# CPULED.net
KiCad netlist of a schematic drawn in Altium Designer
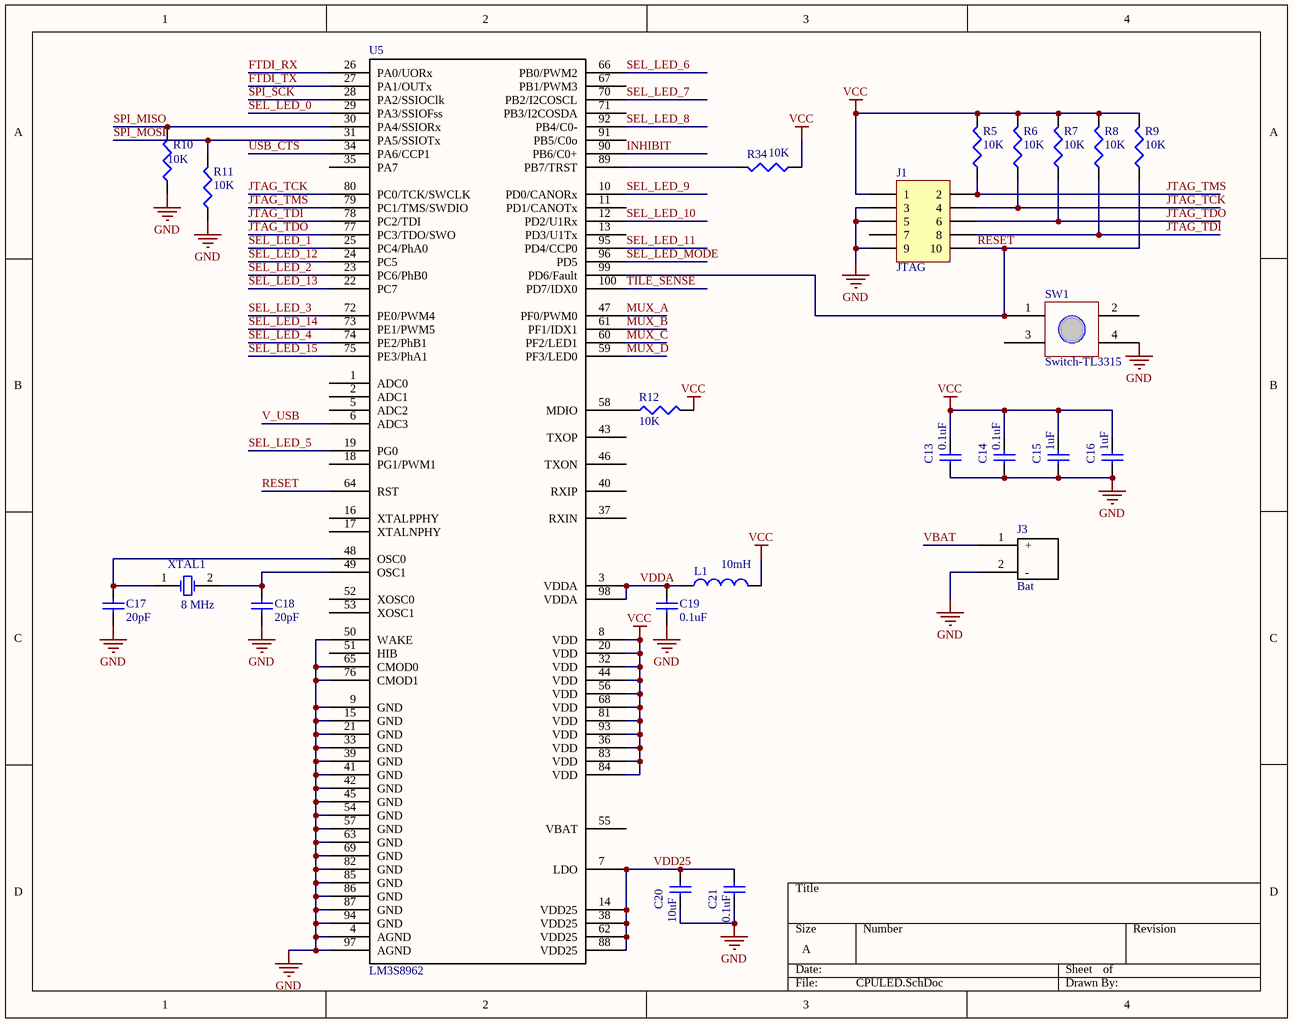
[diagram p0: CPULED.SchDoc]

(export (version "E")
  (design (tool "Eeschema 10.0.6"))
  (components
    (comp (ref "C13")
      (value "0.1uF")
      (footprint "CAPC1005L")
      (description "Capacitor (Semiconductor SIM Model)")
      (fields (field (name "Comment") "Cap Semi") (field (name "PUBLISHER") "Altium Limited"))
      (libsource (lib "Miscellaneous Devices") (part "Cap Semi"))
    )
    (comp (ref "C14")
      (value "0.1uF")
      (footprint "CAPC1005L")
      (description "Capacitor (Semiconductor SIM Model)")
      (fields (field (name "Comment") "Cap Semi") (field (name "PUBLISHER") "Altium Limited"))
      (libsource (lib "Miscellaneous Devices") (part "Cap Semi"))
    )
    (comp (ref "C15")
      (value "1uF")
      (footprint "CAPC1608L")
      (description "Capacitor (Semiconductor SIM Model)")
      (fields (field (name "Comment") "Cap Semi") (field (name "PUBLISHER") "Altium Limited"))
      (libsource (lib "Miscellaneous Devices") (part "Cap Semi"))
    )
    (comp (ref "C16")
      (value "1uF")
      (footprint "CAPC1608L")
      (description "Capacitor (Semiconductor SIM Model)")
      (fields (field (name "Comment") "Cap Semi") (field (name "PUBLISHER") "Altium Limited"))
      (libsource (lib "Miscellaneous Devices") (part "Cap Semi"))
    )
    (comp (ref "C17")
      (value "20pF")
      (footprint "CAPC1005L")
      (description "Capacitor (Semiconductor SIM Model)")
      (fields (field (name "Comment") "Cap Semi") (field (name "PUBLISHER") "Altium Limited"))
      (libsource (lib "Miscellaneous Devices") (part "Cap Semi"))
    )
    (comp (ref "C18")
      (value "20pF")
      (footprint "CAPC1005L")
      (description "Capacitor (Semiconductor SIM Model)")
      (fields (field (name "Comment") "Cap Semi") (field (name "PUBLISHER") "Altium Limited"))
      (libsource (lib "Miscellaneous Devices") (part "Cap Semi"))
    )
    (comp (ref "C19")
      (value "0.1uF")
      (footprint "CAPC1005L")
      (description "Capacitor (Semiconductor SIM Model)")
      (fields (field (name "Comment") "Cap Semi") (field (name "PUBLISHER") "Altium Limited"))
      (libsource (lib "Miscellaneous Devices") (part "Cap Semi"))
    )
    (comp (ref "C20")
      (value "10uF")
      (footprint "CAPC1608L")
      (description "Capacitor (Semiconductor SIM Model)")
      (fields (field (name "Comment") "Cap Semi") (field (name "PUBLISHER") "Altium Limited"))
      (libsource (lib "Miscellaneous Devices") (part "Cap Semi"))
    )
    (comp (ref "C21")
      (value "0.1uF")
      (footprint "CAPC1005L")
      (description "Capacitor (Semiconductor SIM Model)")
      (fields (field (name "Comment") "Cap Semi") (field (name "PUBLISHER") "Altium Limited"))
      (libsource (lib "Miscellaneous Devices") (part "Cap Semi"))
    )
    (comp (ref "J1")
      (value "JTAG")
      (footprint "JTAG-10")
      (description "Header, 5-Pin, Dual row, Right Angle")
      (fields (field (name "PUBLISHER") "Altium Limited"))
      (libsource (lib "Miscellaneous Connectors") (part "Header 5X2H"))
    )
    (comp (ref "J3")
      (value "Bat")
      (footprint "BatteryConnJST")
      (libsource (lib "mrone") (part "BatteryConnJST"))
    )
    (comp (ref "L1")
      (value "10mH")
      (footprint "INDC2012L")
      (description "Inductor")
      (fields (field (name "PUBLISHER") "Altium Limited"))
      (libsource (lib "Miscellaneous Devices") (part "Inductor"))
    )
    (comp (ref "R5")
      (value "10K")
      (footprint "RESC1608L")
      (description "Resistor")
      (fields (field (name "Comment") "Res3") (field (name "PUBLISHER") "Altium Limited"))
      (libsource (lib "Miscellaneous Devices") (part "Res3"))
    )
    (comp (ref "R6")
      (value "10K")
      (footprint "RESC1608L")
      (description "Resistor")
      (fields (field (name "Comment") "Res3") (field (name "PUBLISHER") "Altium Limited"))
      (libsource (lib "Miscellaneous Devices") (part "Res3"))
    )
    (comp (ref "R7")
      (value "10K")
      (footprint "RESC1608L")
      (description "Resistor")
      (fields (field (name "Comment") "Res3") (field (name "PUBLISHER") "Altium Limited"))
      (libsource (lib "Miscellaneous Devices") (part "Res3"))
    )
    (comp (ref "R8")
      (value "10K")
      (footprint "RESC1608L")
      (description "Resistor")
      (fields (field (name "Comment") "Res3") (field (name "PUBLISHER") "Altium Limited"))
      (libsource (lib "Miscellaneous Devices") (part "Res3"))
    )
    (comp (ref "R9")
      (value "10K")
      (footprint "RESC1608L")
      (description "Resistor")
      (fields (field (name "Comment") "Res3") (field (name "PUBLISHER") "Altium Limited"))
      (libsource (lib "Miscellaneous Devices") (part "Res3"))
    )
    (comp (ref "R10")
      (value "10K")
      (footprint "RESC1608L")
      (description "Resistor")
      (fields (field (name "Comment") "Res3") (field (name "PUBLISHER") "Altium Limited"))
      (libsource (lib "Miscellaneous Devices") (part "Res3"))
    )
    (comp (ref "R11")
      (value "10K")
      (footprint "RESC1608L")
      (description "Resistor")
      (fields (field (name "Comment") "Res3") (field (name "PUBLISHER") "Altium Limited"))
      (libsource (lib "Miscellaneous Devices") (part "Res3"))
    )
    (comp (ref "R12")
      (value "10K")
      (footprint "RESC1608L")
      (description "Resistor")
      (fields (field (name "Comment") "Res3") (field (name "PUBLISHER") "Altium Limited"))
      (libsource (lib "Miscellaneous Devices") (part "Res3"))
    )
    (comp (ref "R34")
      (value "10K")
      (footprint "RESC1608L")
      (description "Resistor")
      (fields (field (name "Comment") "Res3") (field (name "PUBLISHER") "Altium Limited"))
      (libsource (lib "Miscellaneous Devices") (part "Res3"))
    )
    (comp (ref "SW1")
      (value "Switch-TL3315")
      (footprint "Switch-TL3315")
      (libsource (lib "mrone") (part "Switch-TL3315"))
    )
    (comp (ref "U5")
      (value "LM3S8962")
      (footprint "LQFP-100")
      (libsource (lib "Schematic Components") (part "LM3S8962"))
    )
    (comp (ref "XTAL1")
      (value "8 MHz")
      (footprint "RESC5025L")
      (description "Crystal Oscillator")
      (fields (field (name "PUBLISHER") "Altium Limited"))
      (libsource (lib "Miscellaneous Devices") (part "XTAL"))
    )
  )
  (nets
    (net (code "1") (name "/FTDI_RX") (class "Default")
      (node (ref "U5") (pin "26") (pinfunction "PA0/UORx_26") (pintype "passive"))
    )
    (net (code "2") (name "/FTDI_TX") (class "Default")
      (node (ref "U5") (pin "27") (pinfunction "PA1/OUTx_27") (pintype "passive"))
    )
    (net (code "3") (name "/INHIBIT") (class "Default")
      (node (ref "U5") (pin "90") (pinfunction "PB6/C0+_90") (pintype "passive"))
    )
    (net (code "4") (name "/JTAG_TCK") (class "Default")
      (node (ref "J1") (pin "4") (pinfunction "4_4") (pintype "passive"))
      (node (ref "R6") (pin "1") (pinfunction "1_1") (pintype "passive"))
      (node (ref "U5") (pin "80") (pinfunction "PC0/TCK/SWCLK_80") (pintype "passive"))
    )
    (net (code "5") (name "/JTAG_TDI") (class "Default")
      (node (ref "J1") (pin "8") (pinfunction "8_8") (pintype "passive"))
      (node (ref "R8") (pin "1") (pinfunction "1_1") (pintype "passive"))
      (node (ref "U5") (pin "78") (pinfunction "PC2/TDI_78") (pintype "passive"))
    )
    (net (code "6") (name "/JTAG_TDO") (class "Default")
      (node (ref "J1") (pin "6") (pinfunction "6_6") (pintype "passive"))
      (node (ref "R7") (pin "1") (pinfunction "1_1") (pintype "passive"))
      (node (ref "U5") (pin "77") (pinfunction "PC3/TDO/SWO_77") (pintype "passive"))
    )
    (net (code "7") (name "/JTAG_TMS") (class "Default")
      (node (ref "J1") (pin "2") (pinfunction "2_2") (pintype "passive"))
      (node (ref "R5") (pin "1") (pinfunction "1_1") (pintype "passive"))
      (node (ref "U5") (pin "79") (pinfunction "PC1/TMS/SWDIO_79") (pintype "passive"))
    )
    (net (code "8") (name "/MUX_A") (class "Default")
      (node (ref "U5") (pin "47") (pinfunction "PF0/PWM0_47") (pintype "passive"))
    )
    (net (code "9") (name "/MUX_B") (class "Default")
      (node (ref "U5") (pin "61") (pinfunction "PF1/IDX1_61") (pintype "passive"))
    )
    (net (code "10") (name "/MUX_C") (class "Default")
      (node (ref "U5") (pin "60") (pinfunction "PF2/LED1_60") (pintype "passive"))
    )
    (net (code "11") (name "/MUX_D") (class "Default")
      (node (ref "U5") (pin "59") (pinfunction "PF3/LED0_59") (pintype "passive"))
    )
    (net (code "12") (name "/RESET") (class "Default")
      (node (ref "J1") (pin "10") (pinfunction "10_10") (pintype "passive"))
      (node (ref "R9") (pin "1") (pinfunction "1_1") (pintype "passive"))
      (node (ref "SW1") (pin "1") (pinfunction "1_1") (pintype "passive"))
      (node (ref "U5") (pin "64") (pinfunction "RST_64") (pintype "passive"))
      (node (ref "U5") (pin "99") (pinfunction "PD6/Fault_99") (pintype "passive"))
    )
    (net (code "13") (name "/SEL_LED_0") (class "Default")
      (node (ref "U5") (pin "29") (pinfunction "PA3/SSIOFss_29") (pintype "passive"))
    )
    (net (code "14") (name "/SEL_LED_1") (class "Default")
      (node (ref "U5") (pin "25") (pinfunction "PC4/PhA0_25") (pintype "passive"))
    )
    (net (code "15") (name "/SEL_LED_2") (class "Default")
      (node (ref "U5") (pin "23") (pinfunction "PC6/PhB0_23") (pintype "passive"))
    )
    (net (code "16") (name "/SEL_LED_3") (class "Default")
      (node (ref "U5") (pin "72") (pinfunction "PE0/PWM4_72") (pintype "passive"))
    )
    (net (code "17") (name "/SEL_LED_4") (class "Default")
      (node (ref "U5") (pin "74") (pinfunction "PE2/PhB1_74") (pintype "passive"))
    )
    (net (code "18") (name "/SEL_LED_5") (class "Default")
      (node (ref "U5") (pin "19") (pinfunction "PG0_19") (pintype "passive"))
    )
    (net (code "19") (name "/SEL_LED_6") (class "Default")
      (node (ref "U5") (pin "66") (pinfunction "PB0/PWM2_66") (pintype "passive"))
    )
    (net (code "20") (name "/SEL_LED_7") (class "Default")
      (node (ref "U5") (pin "70") (pinfunction "PB2/I2COSCL_70") (pintype "passive"))
    )
    (net (code "21") (name "/SEL_LED_8") (class "Default")
      (node (ref "U5") (pin "92") (pinfunction "PB4/C0-_92") (pintype "passive"))
    )
    (net (code "22") (name "/SEL_LED_9") (class "Default")
      (node (ref "U5") (pin "10") (pinfunction "PD0/CANORx_10") (pintype "passive"))
    )
    (net (code "23") (name "/SEL_LED_10") (class "Default")
      (node (ref "U5") (pin "12") (pinfunction "PD2/U1Rx_12") (pintype "passive"))
    )
    (net (code "24") (name "/SEL_LED_11") (class "Default")
      (node (ref "U5") (pin "95") (pinfunction "PD4/CCP0_95") (pintype "passive"))
    )
    (net (code "25") (name "/SEL_LED_12") (class "Default")
      (node (ref "U5") (pin "24") (pinfunction "PC5_24") (pintype "passive"))
    )
    (net (code "26") (name "/SEL_LED_13") (class "Default")
      (node (ref "U5") (pin "22") (pinfunction "PC7_22") (pintype "passive"))
    )
    (net (code "27") (name "/SEL_LED_14") (class "Default")
      (node (ref "U5") (pin "73") (pinfunction "PE1/PWM5_73") (pintype "passive"))
    )
    (net (code "28") (name "/SEL_LED_15") (class "Default")
      (node (ref "U5") (pin "75") (pinfunction "PE3/PhA1_75") (pintype "passive"))
    )
    (net (code "29") (name "/SEL_LED_MODE") (class "Default")
      (node (ref "U5") (pin "96") (pinfunction "PD5_96") (pintype "passive"))
    )
    (net (code "30") (name "/SPI_MISO") (class "Default")
      (node (ref "R10") (pin "2") (pinfunction "2_2") (pintype "passive"))
      (node (ref "U5") (pin "30") (pinfunction "PA4/SSIORx_30") (pintype "passive"))
    )
    (net (code "31") (name "/SPI_MOSI") (class "Default")
      (node (ref "R11") (pin "2") (pinfunction "2_2") (pintype "passive"))
      (node (ref "U5") (pin "31") (pinfunction "PA5/SSIOTx_31") (pintype "passive"))
    )
    (net (code "32") (name "/SPI_SCK") (class "Default")
      (node (ref "U5") (pin "28") (pinfunction "PA2/SSIOClk_28") (pintype "passive"))
    )
    (net (code "33") (name "/TILE_SENSE") (class "Default")
      (node (ref "U5") (pin "100") (pinfunction "PD7/IDX0_100") (pintype "passive"))
    )
    (net (code "34") (name "/USB_CTS") (class "Default")
      (node (ref "U5") (pin "34") (pinfunction "PA6/CCP1_34") (pintype "passive"))
    )
    (net (code "35") (name "/VBAT") (class "Default")
      (node (ref "J3") (pin "1") (pinfunction "+_1") (pintype "passive"))
    )
    (net (code "36") (name "/VDD25") (class "Default")
      (node (ref "C20") (pin "2") (pinfunction "2_2") (pintype "passive"))
      (node (ref "C21") (pin "2") (pinfunction "2_2") (pintype "passive"))
      (node (ref "U5") (pin "14") (pinfunction "VDD25_14") (pintype "passive"))
      (node (ref "U5") (pin "38") (pinfunction "VDD25_38") (pintype "passive"))
      (node (ref "U5") (pin "62") (pinfunction "VDD25_62") (pintype "passive"))
      (node (ref "U5") (pin "7") (pinfunction "LDO_7") (pintype "passive"))
      (node (ref "U5") (pin "88") (pinfunction "VDD25_88") (pintype "passive"))
    )
    (net (code "37") (name "/VDDA") (class "Default")
      (node (ref "C19") (pin "2") (pinfunction "2_2") (pintype "passive"))
      (node (ref "L1") (pin "1") (pinfunction "1_1") (pintype "passive"))
      (node (ref "U5") (pin "3") (pinfunction "VDDA_3") (pintype "passive"))
      (node (ref "U5") (pin "98") (pinfunction "VDDA_98") (pintype "passive"))
    )
    (net (code "38") (name "/V_USB") (class "Default")
      (node (ref "U5") (pin "6") (pinfunction "ADC3_6") (pintype "passive"))
    )
    (net (code "39") (name "GND") (class "Default")
      (node (ref "C13") (pin "1") (pinfunction "1_1") (pintype "passive"))
      (node (ref "C14") (pin "1") (pinfunction "1_1") (pintype "passive"))
      (node (ref "C15") (pin "1") (pinfunction "1_1") (pintype "passive"))
      (node (ref "C16") (pin "1") (pinfunction "1_1") (pintype "passive"))
      (node (ref "C17") (pin "1") (pinfunction "1_1") (pintype "passive"))
      (node (ref "C18") (pin "1") (pinfunction "1_1") (pintype "passive"))
      (node (ref "C19") (pin "1") (pinfunction "1_1") (pintype "passive"))
      (node (ref "C20") (pin "1") (pinfunction "1_1") (pintype "passive"))
      (node (ref "C21") (pin "1") (pinfunction "1_1") (pintype "passive"))
      (node (ref "J1") (pin "3") (pinfunction "3_3") (pintype "passive"))
      (node (ref "J1") (pin "5") (pinfunction "5_5") (pintype "passive"))
      (node (ref "J1") (pin "9") (pinfunction "9_9") (pintype "passive"))
      (node (ref "J3") (pin "2") (pinfunction "-_2") (pintype "passive"))
      (node (ref "R10") (pin "1") (pinfunction "1_1") (pintype "passive"))
      (node (ref "R11") (pin "1") (pinfunction "1_1") (pintype "passive"))
      (node (ref "SW1") (pin "4") (pinfunction "4_4") (pintype "passive"))
      (node (ref "U5") (pin "15") (pinfunction "GND_15") (pintype "passive"))
      (node (ref "U5") (pin "21") (pinfunction "GND_21") (pintype "passive"))
      (node (ref "U5") (pin "33") (pinfunction "GND_33") (pintype "passive"))
      (node (ref "U5") (pin "39") (pinfunction "GND_39") (pintype "passive"))
      (node (ref "U5") (pin "4") (pinfunction "AGND_4") (pintype "passive"))
      (node (ref "U5") (pin "41") (pinfunction "GND_41") (pintype "passive"))
      (node (ref "U5") (pin "42") (pinfunction "GND_42") (pintype "passive"))
      (node (ref "U5") (pin "45") (pinfunction "GND_45") (pintype "passive"))
      (node (ref "U5") (pin "50") (pinfunction "WAKE_50") (pintype "passive"))
      (node (ref "U5") (pin "54") (pinfunction "GND_54") (pintype "passive"))
      (node (ref "U5") (pin "57") (pinfunction "GND_57") (pintype "passive"))
      (node (ref "U5") (pin "63") (pinfunction "GND_63") (pintype "passive"))
      (node (ref "U5") (pin "65") (pinfunction "CMOD0_65") (pintype "passive"))
      (node (ref "U5") (pin "69") (pinfunction "GND_69") (pintype "passive"))
      (node (ref "U5") (pin "76") (pinfunction "CMOD1_76") (pintype "passive"))
      (node (ref "U5") (pin "82") (pinfunction "GND_82") (pintype "passive"))
      (node (ref "U5") (pin "85") (pinfunction "GND_85") (pintype "passive"))
      (node (ref "U5") (pin "86") (pinfunction "GND_86") (pintype "passive"))
      (node (ref "U5") (pin "87") (pinfunction "GND_87") (pintype "passive"))
      (node (ref "U5") (pin "9") (pinfunction "GND_9") (pintype "passive"))
      (node (ref "U5") (pin "94") (pinfunction "GND_94") (pintype "passive"))
      (node (ref "U5") (pin "97") (pinfunction "AGND_97") (pintype "passive"))
    )
    (net (code "40") (name "Net-(U5-MDIO)") (class "Default")
      (node (ref "R12") (pin "1") (pinfunction "1_1") (pintype "passive"))
      (node (ref "U5") (pin "58") (pinfunction "MDIO_58") (pintype "passive"))
    )
    (net (code "41") (name "Net-(U5-OSC0)") (class "Default")
      (node (ref "C17") (pin "2") (pinfunction "2_2") (pintype "passive"))
      (node (ref "U5") (pin "48") (pinfunction "OSC0_48") (pintype "passive"))
      (node (ref "XTAL1") (pin "1") (pinfunction "OSC1_1") (pintype "passive"))
    )
    (net (code "42") (name "Net-(U5-OSC1)") (class "Default")
      (node (ref "C18") (pin "2") (pinfunction "2_2") (pintype "passive"))
      (node (ref "U5") (pin "49") (pinfunction "OSC1_49") (pintype "passive"))
      (node (ref "XTAL1") (pin "2") (pinfunction "OSC2_2") (pintype "passive"))
    )
    (net (code "43") (name "Net-(U5-PB7{slash}TRST)") (class "Default")
      (node (ref "R34") (pin "2") (pinfunction "2_2") (pintype "passive"))
      (node (ref "U5") (pin "89") (pinfunction "PB7/TRST_89") (pintype "passive"))
    )
    (net (code "44") (name "VCC") (class "Default")
      (node (ref "C13") (pin "2") (pinfunction "2_2") (pintype "passive"))
      (node (ref "C14") (pin "2") (pinfunction "2_2") (pintype "passive"))
      (node (ref "C15") (pin "2") (pinfunction "2_2") (pintype "passive"))
      (node (ref "C16") (pin "2") (pinfunction "2_2") (pintype "passive"))
      (node (ref "J1") (pin "1") (pinfunction "1_1") (pintype "passive"))
      (node (ref "L1") (pin "2") (pinfunction "2_2") (pintype "passive"))
      (node (ref "R12") (pin "2") (pinfunction "2_2") (pintype "passive"))
      (node (ref "R34") (pin "1") (pinfunction "1_1") (pintype "passive"))
      (node (ref "R5") (pin "2") (pinfunction "2_2") (pintype "passive"))
      (node (ref "R6") (pin "2") (pinfunction "2_2") (pintype "passive"))
      (node (ref "R7") (pin "2") (pinfunction "2_2") (pintype "passive"))
      (node (ref "R8") (pin "2") (pinfunction "2_2") (pintype "passive"))
      (node (ref "R9") (pin "2") (pinfunction "2_2") (pintype "passive"))
      (node (ref "U5") (pin "20") (pinfunction "VDD_20") (pintype "passive"))
      (node (ref "U5") (pin "32") (pinfunction "VDD_32") (pintype "passive"))
      (node (ref "U5") (pin "36") (pinfunction "VDD_36") (pintype "passive"))
      (node (ref "U5") (pin "44") (pinfunction "VDD_44") (pintype "passive"))
      (node (ref "U5") (pin "56") (pinfunction "VDD_56") (pintype "passive"))
      (node (ref "U5") (pin "68") (pinfunction "VDD_68") (pintype "passive"))
      (node (ref "U5") (pin "8") (pinfunction "VDD_8") (pintype "passive"))
      (node (ref "U5") (pin "81") (pinfunction "VDD_81") (pintype "passive"))
      (node (ref "U5") (pin "83") (pinfunction "VDD_83") (pintype "passive"))
      (node (ref "U5") (pin "84") (pinfunction "VDD_84") (pintype "passive"))
      (node (ref "U5") (pin "93") (pinfunction "VDD_93") (pintype "passive"))
    )
    (net (code "45") (name "unconnected-(J1-Pad7)") (class "Default")
      (node (ref "J1") (pin "7") (pinfunction "7_7") (pintype "passive"))
    )
    (net (code "46") (name "unconnected-(SW1-Pad2)") (class "Default")
      (node (ref "SW1") (pin "2") (pinfunction "2_2") (pintype "passive"))
    )
    (net (code "47") (name "unconnected-(SW1-Pad3)") (class "Default")
      (node (ref "SW1") (pin "3") (pinfunction "3_3") (pintype "passive"))
    )
    (net (code "48") (name "unconnected-(U5-ADC0-Pad1)") (class "Default")
      (node (ref "U5") (pin "1") (pinfunction "ADC0_1") (pintype "passive"))
    )
    (net (code "49") (name "unconnected-(U5-ADC1-Pad2)") (class "Default")
      (node (ref "U5") (pin "2") (pinfunction "ADC1_2") (pintype "passive"))
    )
    (net (code "50") (name "unconnected-(U5-ADC2-Pad5)") (class "Default")
      (node (ref "U5") (pin "5") (pinfunction "ADC2_5") (pintype "passive"))
    )
    (net (code "51") (name "unconnected-(U5-HIB-Pad51)") (class "Default")
      (node (ref "U5") (pin "51") (pinfunction "HIB_51") (pintype "passive"))
    )
    (net (code "52") (name "unconnected-(U5-PA7-Pad35)") (class "Default")
      (node (ref "U5") (pin "35") (pinfunction "PA7_35") (pintype "passive"))
    )
    (net (code "53") (name "unconnected-(U5-PB1{slash}PWM3-Pad67)") (class "Default")
      (node (ref "U5") (pin "67") (pinfunction "PB1/PWM3_67") (pintype "passive"))
    )
    (net (code "54") (name "unconnected-(U5-PB3{slash}I2COSDA-Pad71)") (class "Default")
      (node (ref "U5") (pin "71") (pinfunction "PB3/I2COSDA_71") (pintype "passive"))
    )
    (net (code "55") (name "unconnected-(U5-PB5{slash}C0o-Pad91)") (class "Default")
      (node (ref "U5") (pin "91") (pinfunction "PB5/C0o_91") (pintype "passive"))
    )
    (net (code "56") (name "unconnected-(U5-PD1{slash}CANOTx-Pad11)") (class "Default")
      (node (ref "U5") (pin "11") (pinfunction "PD1/CANOTx_11") (pintype "passive"))
    )
    (net (code "57") (name "unconnected-(U5-PD3{slash}U1Tx-Pad13)") (class "Default")
      (node (ref "U5") (pin "13") (pinfunction "PD3/U1Tx_13") (pintype "passive"))
    )
    (net (code "58") (name "unconnected-(U5-PG1{slash}PWM1-Pad18)") (class "Default")
      (node (ref "U5") (pin "18") (pinfunction "PG1/PWM1_18") (pintype "passive"))
    )
    (net (code "59") (name "unconnected-(U5-RXIN-Pad37)") (class "Default")
      (node (ref "U5") (pin "37") (pinfunction "RXIN_37") (pintype "passive"))
    )
    (net (code "60") (name "unconnected-(U5-RXIP-Pad40)") (class "Default")
      (node (ref "U5") (pin "40") (pinfunction "RXIP_40") (pintype "passive"))
    )
    (net (code "61") (name "unconnected-(U5-TXON-Pad46)") (class "Default")
      (node (ref "U5") (pin "46") (pinfunction "TXON_46") (pintype "passive"))
    )
    (net (code "62") (name "unconnected-(U5-TXOP-Pad43)") (class "Default")
      (node (ref "U5") (pin "43") (pinfunction "TXOP_43") (pintype "passive"))
    )
    (net (code "63") (name "unconnected-(U5-VBAT-Pad55)") (class "Default")
      (node (ref "U5") (pin "55") (pinfunction "VBAT_55") (pintype "passive"))
    )
    (net (code "64") (name "unconnected-(U5-XOSC0-Pad52)") (class "Default")
      (node (ref "U5") (pin "52") (pinfunction "XOSC0_52") (pintype "passive"))
    )
    (net (code "65") (name "unconnected-(U5-XOSC1-Pad53)") (class "Default")
      (node (ref "U5") (pin "53") (pinfunction "XOSC1_53") (pintype "passive"))
    )
    (net (code "66") (name "unconnected-(U5-XTALNPHY-Pad17)") (class "Default")
      (node (ref "U5") (pin "17") (pinfunction "XTALNPHY_17") (pintype "passive"))
    )
    (net (code "67") (name "unconnected-(U5-XTALPPHY-Pad16)") (class "Default")
      (node (ref "U5") (pin "16") (pinfunction "XTALPPHY_16") (pintype "passive"))
    )
  )
)
